# WIFIBT_AP6256.net
KiCad netlist of a schematic drawn in Altium Designer
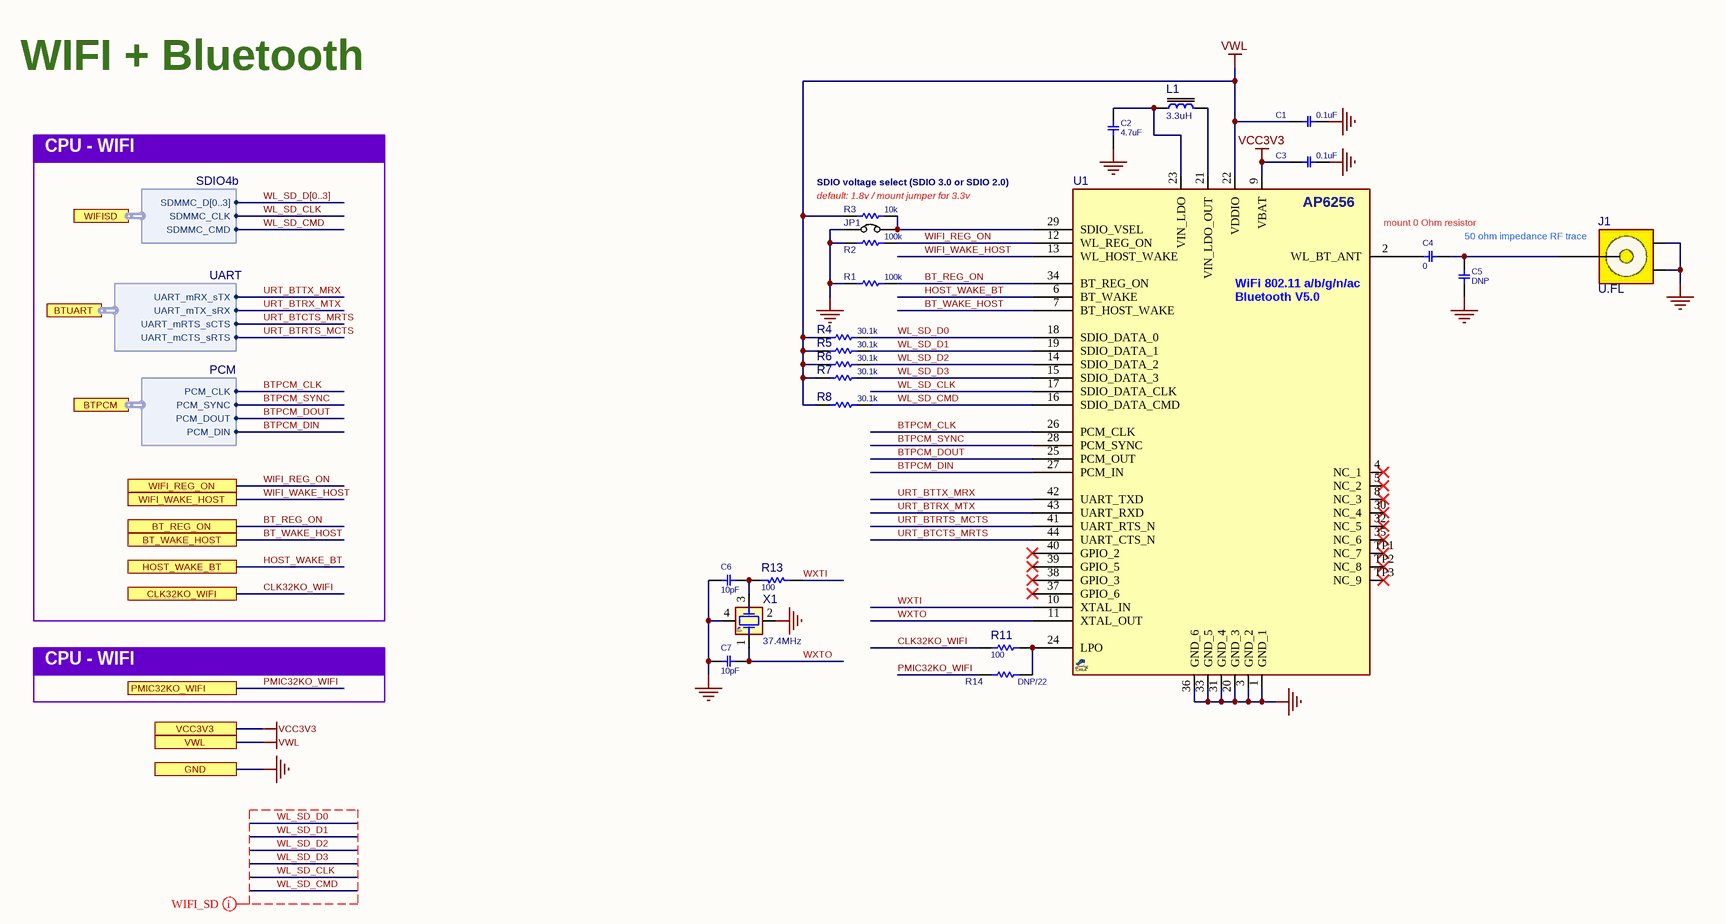
[diagram p0: WIFIBT_AP6256.SchDoc]

(export (version "E")
  (design (tool "Eeschema 10.0.6"))
  (components
    (comp (ref "C1")
      (value "0.1uF")
      (footprint "C0402")
      (description "CAP, MLCC")
      (fields (field (name "MANF_P#") "GRM155R71H104KE14D") (field (name "MANF") "Murata"))
      (libsource (lib "passive_smd") (part "CAP_SMD_MLCC"))
    )
    (comp (ref "C2")
      (value "4.7uF")
      (footprint "C0402")
      (description "CAP, MLCC")
      (fields (field (name "MANF_P#") "LMK105BBJ475MVLF") (field (name "MANF") "Taiyo Yuden"))
      (libsource (lib "passive_smd") (part "CAP_SMD_MLCC"))
    )
    (comp (ref "C3")
      (value "0.1uF")
      (footprint "C0402")
      (description "CAP, MLCC")
      (fields (field (name "MANF_P#") "GRM155R71H104KE14D") (field (name "MANF") "Murata"))
      (libsource (lib "passive_smd") (part "CAP_SMD_MLCC"))
    )
    (comp (ref "C4")
      (value "0")
      (footprint "C0402")
      (description "CAP, MLCC, 1nF, 50V, C0G, 10%, 0402")
      (fields (field (name "MANF_P#") "MANF_PART#") (field (name "MANF") "Murata"))
      (libsource (lib "passive_smd") (part "CAP_SMD_MLCC"))
    )
    (comp (ref "C5")
      (value "DNP")
      (footprint "C0402")
      (description "CAP, MLCC, 1nF, 50V, C0G, 10%, 0402")
      (fields (field (name "MANF_P#") "MANF_PART#") (field (name "MANF") "Murata"))
      (libsource (lib "passive_smd") (part "CAP_SMD_MLCC"))
    )
    (comp (ref "C6")
      (value "10pF")
      (footprint "C0402")
      (description "CAP, MLCC")
      (fields (field (name "MANF_P#") "CC0402JRNPO9BN100") (field (name "MANF") "Yageo"))
      (libsource (lib "passive_smd") (part "CAP_SMD_MLCC"))
    )
    (comp (ref "C7")
      (value "10pF")
      (footprint "C0402")
      (description "CAP, MLCC")
      (fields (field (name "MANF_P#") "CC0402JRNPO9BN100") (field (name "MANF") "Yageo"))
      (libsource (lib "passive_smd") (part "CAP_SMD_MLCC"))
    )
    (comp (ref "J1")
      (value "U.FL")
      (footprint "UFL")
      (description "CONN, RF, U.FL, STRAIGHT, Ultra Miniature Coaxial")
      (fields
        (field (name "MANF_P#") "CONUFL001-SMD, U.FL-R-SMT-1(10), 128-0711-201")
        (field (name "MANF") "Linx, Hirose, Cinch")
      )
      (libsource (lib "conn_rf") (part "CONN_RF_UFL"))
    )
    (comp (ref "JP1")
      (value "JMPSOLDER")
      (footprint "JP_60X100")
      (description "JUMPER, HEADER 2PIN")
      (fields (field (name "MANF") "MANF") (field (name "MANF_P#") "MANF_P#"))
      (libsource (lib "test-tp_jumper") (part "JUMPER_SOLDER"))
    )
    (comp (ref "L1")
      (value "3.3uH")
      (footprint "L_3")
      (description "INDUCTOR, POWER, SMD")
      (fields (field (name "MANF") "Bourns") (field (name "MANF_P#") "SRN3010-3R3M"))
      (libsource (lib "passive_smd") (part "INDPWR_SMD"))
    )
    (comp (ref "R1")
      (value "100k")
      (footprint "R0402")
      (description "RESISTOR, SMD")
      (libsource (lib "passive_res_smd") (part "RES_SMD"))
    )
    (comp (ref "R2")
      (value "100k")
      (footprint "R0402")
      (description "RESISTOR, SMD")
      (libsource (lib "passive_res_smd") (part "RES_SMD"))
    )
    (comp (ref "R3")
      (value "10k")
      (footprint "R0402")
      (description "RESISTOR, SMD")
      (libsource (lib "passive_res_smd") (part "RES_SMD"))
    )
    (comp (ref "R4")
      (value "30.1k")
      (footprint "R0402")
      (description "RESISTOR, SMD")
      (libsource (lib "passive_res_smd") (part "RES_SMD"))
    )
    (comp (ref "R5")
      (value "30.1k")
      (footprint "R0402")
      (description "RESISTOR, SMD")
      (libsource (lib "passive_res_smd") (part "RES_SMD"))
    )
    (comp (ref "R6")
      (value "30.1k")
      (footprint "R0402")
      (description "RESISTOR, SMD")
      (libsource (lib "passive_res_smd") (part "RES_SMD"))
    )
    (comp (ref "R7")
      (value "30.1k")
      (footprint "R0402")
      (description "RESISTOR, SMD")
      (libsource (lib "passive_res_smd") (part "RES_SMD"))
    )
    (comp (ref "R8")
      (value "30.1k")
      (footprint "R0402")
      (description "RESISTOR, SMD")
      (libsource (lib "passive_res_smd") (part "RES_SMD"))
    )
    (comp (ref "R11")
      (value "100")
      (footprint "R0402")
      (description "RESISTOR, SMD")
      (libsource (lib "passive_res_smd") (part "RES_SMD"))
    )
    (comp (ref "R13")
      (value "100")
      (footprint "R0402")
      (description "RESISTOR, SMD")
      (libsource (lib "passive_res_smd") (part "RES_SMD"))
    )
    (comp (ref "R14")
      (value "DNP/22")
      (footprint "R0402")
      (description "RESISTOR, SMD")
      (libsource (lib "passive_res_smd") (part "RES_SMD"))
    )
    (comp (ref "U1")
      (value "AP6256")
      (footprint "AP625X_44_12X12")
      (description "WiFi with Bluetooth 5.0")
      (fields (field (name "MANF") "AMPAK"))
      (libsource (lib "module_wifi") (part "AP6256"))
    )
    (comp (ref "X1")
      (value "37.4MHz")
      (footprint "XTL_4_2016")
      (description "CRYSTAL")
      (fields (field (name "MANF") "Murata") (field (name "MANF_P#") "XRCGB37M400F1S2FR0"))
      (libsource (lib "crystal") (part "XTL_4_40MHz_3225F"))
    )
  )
  (nets
    (net (code "4") (name "/BTPCM_CLK") (class "Default")
      (node (ref "U1") (pin "26") (pinfunction "PCM_CLK_26") (pintype "passive"))
    )
    (net (code "5") (name "/BTPCM_DIN") (class "Default")
      (node (ref "U1") (pin "27") (pinfunction "PCM_IN_27") (pintype "passive"))
    )
    (net (code "6") (name "/BTPCM_DOUT") (class "Default")
      (node (ref "U1") (pin "25") (pinfunction "PCM_OUT_25") (pintype "passive"))
    )
    (net (code "7") (name "/BTPCM_SYNC") (class "Default")
      (node (ref "U1") (pin "28") (pinfunction "PCM_SYNC_28") (pintype "passive"))
    )
    (net (code "8") (name "/BT_REG_ON") (class "Default")
      (node (ref "R1") (pin "1") (pinfunction "1_1") (pintype "passive"))
      (node (ref "U1") (pin "34") (pinfunction "BT_REG_ON_34") (pintype "passive"))
    )
    (net (code "9") (name "/BT_WAKE_HOST") (class "Default")
      (node (ref "U1") (pin "7") (pinfunction "BT_HOST_WAKE_7") (pintype "passive"))
    )
    (net (code "10") (name "/CLK32KO_WIFI") (class "Default")
      (node (ref "R11") (pin "2") (pinfunction "2_2") (pintype "passive"))
    )
    (net (code "11") (name "/HOST_WAKE_BT") (class "Default")
      (node (ref "U1") (pin "6") (pinfunction "BT_WAKE_6") (pintype "passive"))
    )
    (net (code "12") (name "/PMIC32KO_WIFI") (class "Default")
      (node (ref "R14") (pin "2") (pinfunction "2_2") (pintype "passive"))
    )
    (net (code "13") (name "/URT_BTCTS_MRTS") (class "Default")
      (node (ref "U1") (pin "44") (pinfunction "UART_CTS_N_44") (pintype "passive"))
    )
    (net (code "14") (name "/URT_BTRTS_MCTS") (class "Default")
      (node (ref "U1") (pin "41") (pinfunction "UART_RTS_N_41") (pintype "passive"))
    )
    (net (code "15") (name "/URT_BTRX_MTX") (class "Default")
      (node (ref "U1") (pin "43") (pinfunction "UART_RXD_43") (pintype "passive"))
    )
    (net (code "16") (name "/URT_BTTX_MRX") (class "Default")
      (node (ref "U1") (pin "42") (pinfunction "UART_TXD_42") (pintype "passive"))
    )
    (net (code "17") (name "/WIFI_REG_ON") (class "Default")
      (node (ref "R2") (pin "1") (pinfunction "1_1") (pintype "passive"))
      (node (ref "U1") (pin "12") (pinfunction "WL_REG_ON_12") (pintype "passive"))
    )
    (net (code "18") (name "/WIFI_WAKE_HOST") (class "Default")
      (node (ref "U1") (pin "13") (pinfunction "WL_HOST_WAKE_13") (pintype "passive"))
    )
    (net (code "19") (name "/WL_SD_CLK") (class "Default")
      (node (ref "U1") (pin "17") (pinfunction "SDIO_DATA_CLK_17") (pintype "passive"))
    )
    (net (code "20") (name "/WL_SD_CMD") (class "Default")
      (node (ref "R8") (pin "1") (pinfunction "1_1") (pintype "passive"))
      (node (ref "U1") (pin "16") (pinfunction "SDIO_DATA_CMD_16") (pintype "passive"))
    )
    (net (code "21") (name "/WL_SD_D0") (class "Default")
      (node (ref "R4") (pin "1") (pinfunction "1_1") (pintype "passive"))
      (node (ref "U1") (pin "18") (pinfunction "SDIO_DATA_0_18") (pintype "passive"))
    )
    (net (code "22") (name "/WL_SD_D1") (class "Default")
      (node (ref "R5") (pin "1") (pinfunction "1_1") (pintype "passive"))
      (node (ref "U1") (pin "19") (pinfunction "SDIO_DATA_1_19") (pintype "passive"))
    )
    (net (code "23") (name "/WL_SD_D2") (class "Default")
      (node (ref "R6") (pin "1") (pinfunction "1_1") (pintype "passive"))
      (node (ref "U1") (pin "14") (pinfunction "SDIO_DATA_2_14") (pintype "passive"))
    )
    (net (code "24") (name "/WL_SD_D3") (class "Default")
      (node (ref "R7") (pin "1") (pinfunction "1_1") (pintype "passive"))
      (node (ref "U1") (pin "15") (pinfunction "SDIO_DATA_3_15") (pintype "passive"))
    )
    (net (code "26") (name "/WXTI") (class "Default")
      (node (ref "R13") (pin "2") (pinfunction "2_2") (pintype "passive"))
      (node (ref "U1") (pin "10") (pinfunction "XTAL_IN_10") (pintype "passive"))
    )
    (net (code "27") (name "/WXTO") (class "Default")
      (node (ref "C7") (pin "1") (pinfunction "1_1") (pintype "passive"))
      (node (ref "U1") (pin "11") (pinfunction "XTAL_OUT_11") (pintype "passive"))
      (node (ref "X1") (pin "1") (pinfunction "XA_1") (pintype "passive"))
    )
    (net (code "31") (name "GND") (class "Default")
      (node (ref "C1") (pin "1") (pinfunction "1_1") (pintype "passive"))
      (node (ref "C2") (pin "2") (pinfunction "2_2") (pintype "passive"))
      (node (ref "C3") (pin "1") (pinfunction "1_1") (pintype "passive"))
      (node (ref "C5") (pin "2") (pinfunction "2_2") (pintype "passive"))
      (node (ref "C6") (pin "2") (pinfunction "2_2") (pintype "passive"))
      (node (ref "C7") (pin "2") (pinfunction "2_2") (pintype "passive"))
      (node (ref "J1") (pin "2") (pinfunction "G1_2") (pintype "passive"))
      (node (ref "J1") (pin "3") (pinfunction "G2_3") (pintype "passive"))
      (node (ref "JP1") (pin "1") (pinfunction "1_1") (pintype "passive"))
      (node (ref "R1") (pin "2") (pinfunction "2_2") (pintype "passive"))
      (node (ref "R2") (pin "2") (pinfunction "2_2") (pintype "passive"))
      (node (ref "U1") (pin "1") (pinfunction "GND_1_1") (pintype "passive"))
      (node (ref "U1") (pin "20") (pinfunction "GND_3_20") (pintype "passive"))
      (node (ref "U1") (pin "3") (pinfunction "GND_2_3") (pintype "passive"))
      (node (ref "U1") (pin "31") (pinfunction "GND_4_31") (pintype "passive"))
      (node (ref "U1") (pin "33") (pinfunction "GND_5_33") (pintype "passive"))
      (node (ref "U1") (pin "36") (pinfunction "GND_6_36") (pintype "passive"))
      (node (ref "X1") (pin "2") (pinfunction "GND1_2") (pintype "passive"))
      (node (ref "X1") (pin "4") (pinfunction "GND2_4") (pintype "passive"))
    )
    (net (code "32") (name "Net-(J1-SIG)") (class "Default")
      (node (ref "C4") (pin "1") (pinfunction "1_1") (pintype "passive"))
      (node (ref "C5") (pin "1") (pinfunction "1_1") (pintype "passive"))
      (node (ref "J1") (pin "1") (pinfunction "SIG_1") (pintype "passive"))
    )
    (net (code "33") (name "Net-(U1-LPO)") (class "Default")
      (node (ref "R11") (pin "1") (pinfunction "1_1") (pintype "passive"))
      (node (ref "R14") (pin "1") (pinfunction "1_1") (pintype "passive"))
      (node (ref "U1") (pin "24") (pinfunction "LPO_24") (pintype "passive"))
    )
    (net (code "34") (name "Net-(U1-SDIO_VSEL)") (class "Default")
      (node (ref "JP1") (pin "2") (pinfunction "2_2") (pintype "passive"))
      (node (ref "R3") (pin "1") (pinfunction "1_1") (pintype "passive"))
      (node (ref "U1") (pin "29") (pinfunction "SDIO_VSEL_29") (pintype "passive"))
    )
    (net (code "35") (name "Net-(U1-VIN_LDO)") (class "Default")
      (node (ref "C2") (pin "1") (pinfunction "1_1") (pintype "passive"))
      (node (ref "L1") (pin "1") (pinfunction "1_1") (pintype "passive"))
      (node (ref "U1") (pin "23") (pinfunction "VIN_LDO_23") (pintype "passive"))
    )
    (net (code "36") (name "Net-(U1-VIN_LDO_OUT)") (class "Default")
      (node (ref "L1") (pin "2") (pinfunction "2_2") (pintype "passive"))
      (node (ref "U1") (pin "21") (pinfunction "VIN_LDO_OUT_21") (pintype "passive"))
    )
    (net (code "37") (name "Net-(U1-WL_BT_ANT)") (class "Default")
      (node (ref "C4") (pin "2") (pinfunction "2_2") (pintype "passive"))
      (node (ref "U1") (pin "2") (pinfunction "WL_BT_ANT_2") (pintype "passive"))
    )
    (net (code "38") (name "Net-(X1-XB)") (class "Default")
      (node (ref "C6") (pin "1") (pinfunction "1_1") (pintype "passive"))
      (node (ref "R13") (pin "1") (pinfunction "1_1") (pintype "passive"))
      (node (ref "X1") (pin "3") (pinfunction "XB_3") (pintype "passive"))
    )
    (net (code "39") (name "VCC3V3") (class "Default")
      (node (ref "C3") (pin "2") (pinfunction "2_2") (pintype "passive"))
      (node (ref "U1") (pin "9") (pinfunction "VBAT_9") (pintype "passive"))
    )
    (net (code "40") (name "VWL") (class "Default")
      (node (ref "C1") (pin "2") (pinfunction "2_2") (pintype "passive"))
      (node (ref "R3") (pin "2") (pinfunction "2_2") (pintype "passive"))
      (node (ref "R4") (pin "2") (pinfunction "2_2") (pintype "passive"))
      (node (ref "R5") (pin "2") (pinfunction "2_2") (pintype "passive"))
      (node (ref "R6") (pin "2") (pinfunction "2_2") (pintype "passive"))
      (node (ref "R7") (pin "2") (pinfunction "2_2") (pintype "passive"))
      (node (ref "R8") (pin "2") (pinfunction "2_2") (pintype "passive"))
      (node (ref "U1") (pin "22") (pinfunction "VDDIO_22") (pintype "passive"))
    )
    (net (code "41") (name "unconnected-(U1-GPIO_2-Pad40)") (class "Default")
      (node (ref "U1") (pin "40") (pinfunction "GPIO_2_40") (pintype "passive+no_connect"))
    )
    (net (code "42") (name "unconnected-(U1-GPIO_3-Pad38)") (class "Default")
      (node (ref "U1") (pin "38") (pinfunction "GPIO_3_38") (pintype "passive+no_connect"))
    )
    (net (code "43") (name "unconnected-(U1-GPIO_5-Pad39)") (class "Default")
      (node (ref "U1") (pin "39") (pinfunction "GPIO_5_39") (pintype "passive+no_connect"))
    )
    (net (code "44") (name "unconnected-(U1-GPIO_6-Pad37)") (class "Default")
      (node (ref "U1") (pin "37") (pinfunction "GPIO_6_37") (pintype "passive+no_connect"))
    )
    (net (code "45") (name "unconnected-(U1-NC_1-Pad4)") (class "Default")
      (node (ref "U1") (pin "4") (pinfunction "NC_1_4") (pintype "passive+no_connect"))
    )
    (net (code "46") (name "unconnected-(U1-NC_2-Pad5)") (class "Default")
      (node (ref "U1") (pin "5") (pinfunction "NC_2_5") (pintype "passive+no_connect"))
    )
    (net (code "47") (name "unconnected-(U1-NC_3-Pad8)") (class "Default")
      (node (ref "U1") (pin "8") (pinfunction "NC_3_8") (pintype "passive+no_connect"))
    )
    (net (code "48") (name "unconnected-(U1-NC_4-Pad30)") (class "Default")
      (node (ref "U1") (pin "30") (pinfunction "NC_4_30") (pintype "passive+no_connect"))
    )
    (net (code "49") (name "unconnected-(U1-NC_5-Pad32)") (class "Default")
      (node (ref "U1") (pin "32") (pinfunction "NC_5_32") (pintype "passive+no_connect"))
    )
    (net (code "50") (name "unconnected-(U1-NC_6-Pad35)") (class "Default")
      (node (ref "U1") (pin "35") (pinfunction "NC_6_35") (pintype "passive+no_connect"))
    )
    (net (code "51") (name "unconnected-(U1-NC_7-PadTP1)") (class "Default")
      (node (ref "U1") (pin "TP1") (pinfunction "NC_7_TP1") (pintype "passive+no_connect"))
    )
    (net (code "52") (name "unconnected-(U1-NC_8-PadTP2)") (class "Default")
      (node (ref "U1") (pin "TP2") (pinfunction "NC_8_TP2") (pintype "passive+no_connect"))
    )
    (net (code "53") (name "unconnected-(U1-NC_9-PadTP3)") (class "Default")
      (node (ref "U1") (pin "TP3") (pinfunction "NC_9_TP3") (pintype "passive+no_connect"))
    )
  )
)
